# btnsm_a_bit_larger.net
KiCad netlist of a schematic drawn in EAGLE
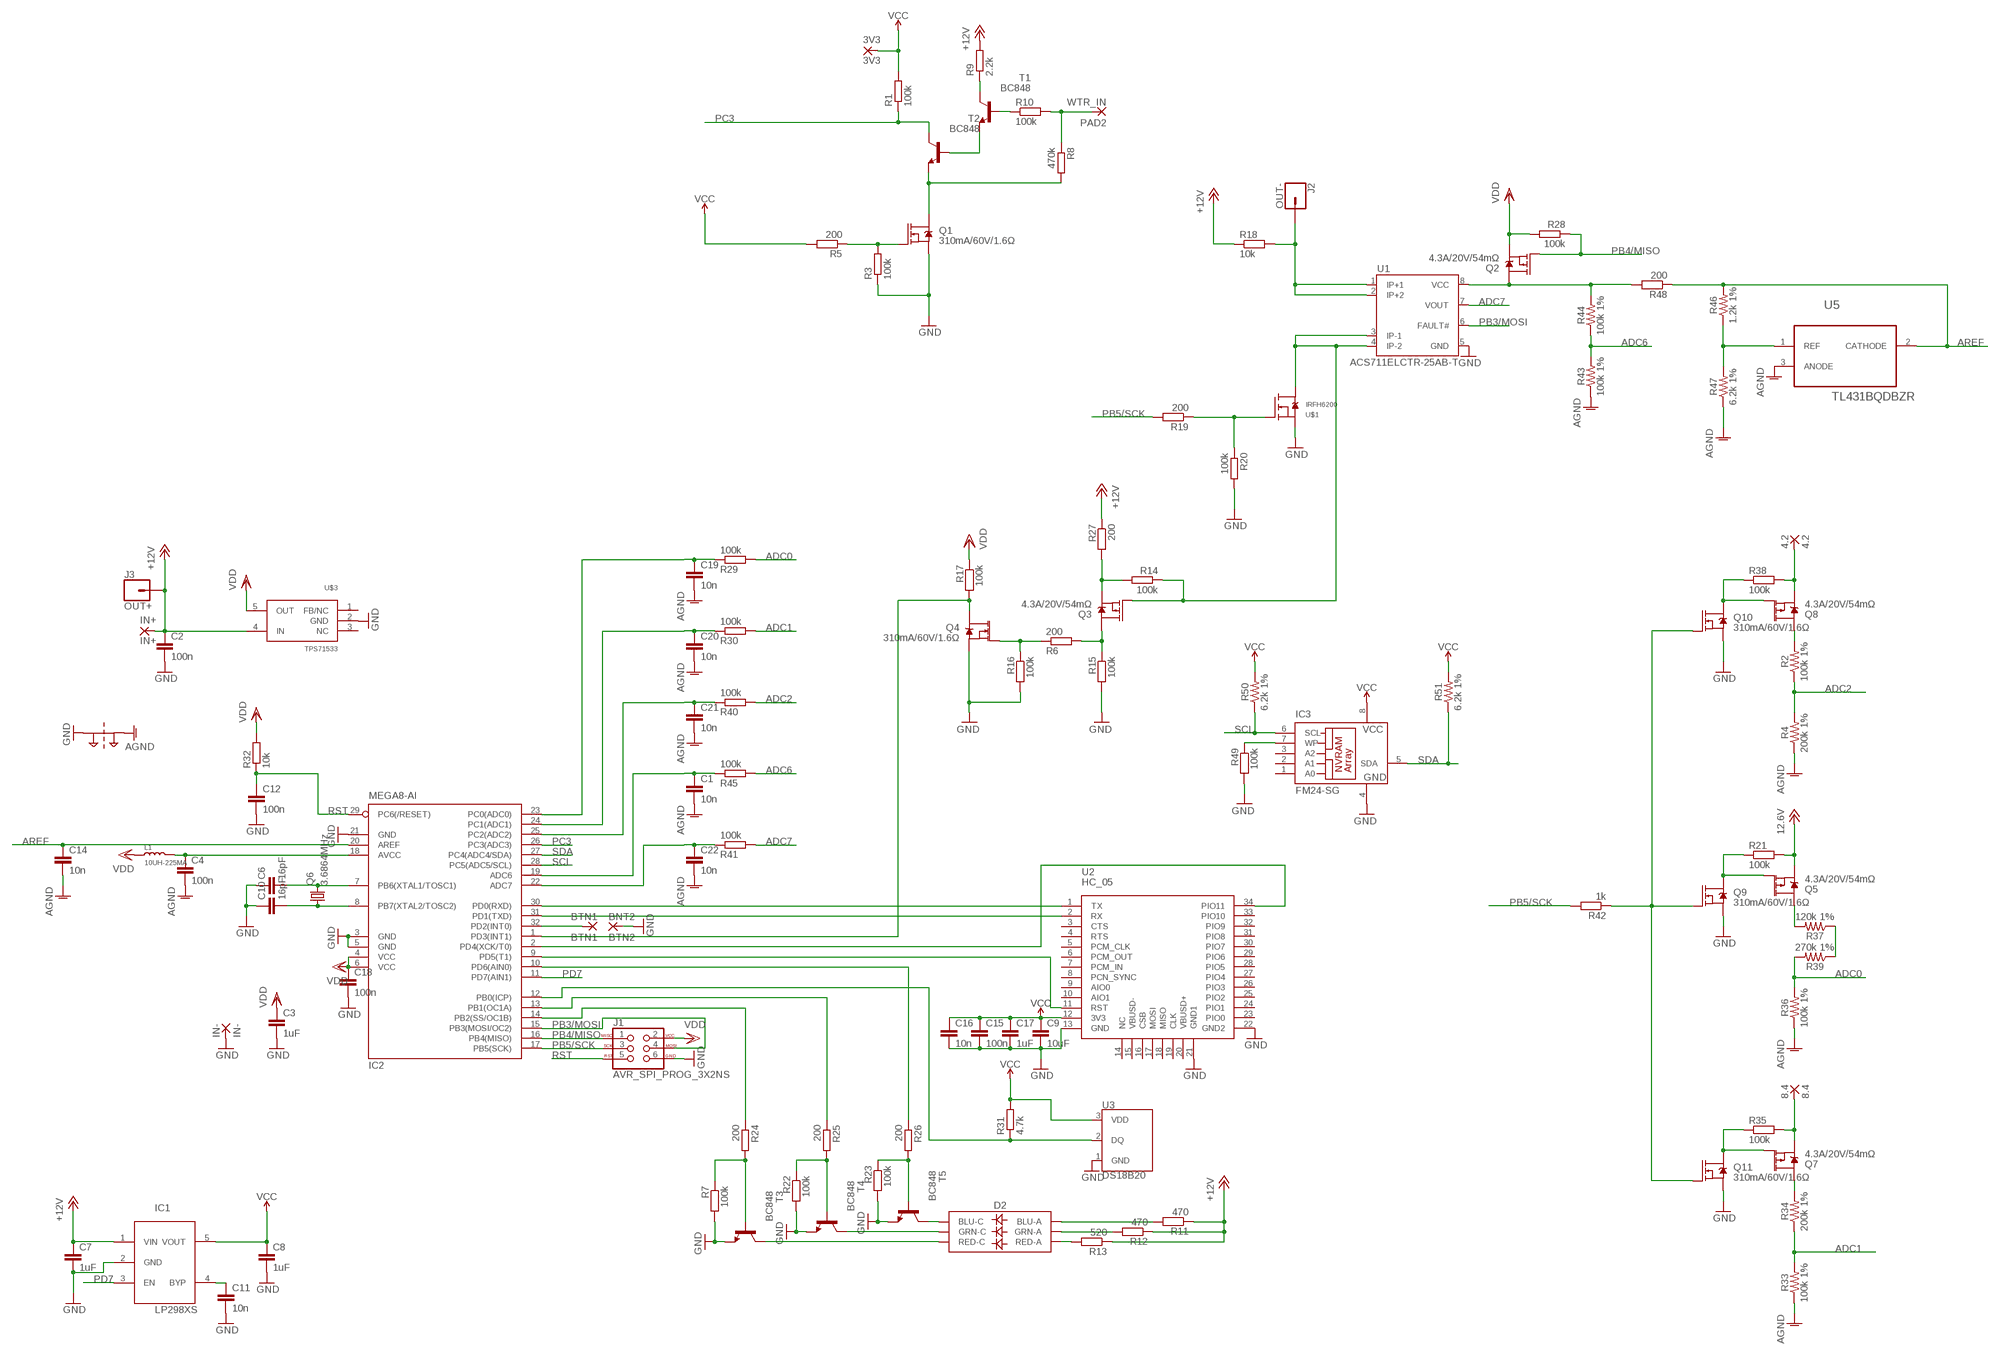
[diagram p0: schematic, sheet 1]

(export (version "E")
  (design (tool "Eeschema 10.0.6"))
  (components
    (comp (ref "3V3")
      (value "3V3")
      (footprint "eagle-import:SMD1,27-2,54")
      (libsource (lib "eagle-import") (part "WIREPADSMD1,27-254"))
    )
    (comp (ref "4.2")
      (value "4.2")
      (footprint "eagle-import:SMD1,27-2,54")
      (libsource (lib "eagle-import") (part "WIREPADSMD1,27-254"))
    )
    (comp (ref "8.4")
      (value "8.4")
      (footprint "eagle-import:SMD1,27-2,54")
      (libsource (lib "eagle-import") (part "WIREPADSMD1,27-254"))
    )
    (comp (ref "BTN1")
      (value "BTN1")
      (footprint "eagle-import:1,6_0,9")
      (libsource (lib "eagle-import") (part "1,6/0,9"))
    )
    (comp (ref "BTN2")
      (value "BNT2")
      (footprint "eagle-import:1,6_0,9")
      (libsource (lib "eagle-import") (part "1,6/0,9"))
    )
    (comp (ref "C1")
      (value "10n")
      (footprint "eagle-import:C0402")
      (libsource (lib "eagle-import") (part "C-EUC0402"))
    )
    (comp (ref "C2")
      (value "100n")
      (footprint "eagle-import:C0603")
      (libsource (lib "eagle-import") (part "C-EUC0603"))
    )
    (comp (ref "C3")
      (value "1uF")
      (footprint "eagle-import:C0805")
      (libsource (lib "eagle-import") (part "C-EUC0805"))
    )
    (comp (ref "C4")
      (value "100n")
      (footprint "eagle-import:C0402")
      (libsource (lib "eagle-import") (part "C-EUC0402"))
    )
    (comp (ref "C6")
      (value "16pF")
      (footprint "eagle-import:C0402")
      (libsource (lib "eagle-import") (part "C-EUC0402"))
    )
    (comp (ref "C7")
      (value "1uF")
      (footprint "eagle-import:C0805")
      (libsource (lib "eagle-import") (part "C-EUC0805"))
    )
    (comp (ref "C8")
      (value "1uF")
      (footprint "eagle-import:C0805")
      (libsource (lib "eagle-import") (part "C-EUC0805"))
    )
    (comp (ref "C9")
      (value "10uF")
      (footprint "eagle-import:C0805")
      (libsource (lib "eagle-import") (part "C-EUC0805"))
    )
    (comp (ref "C10")
      (value "16pF")
      (footprint "eagle-import:C0402")
      (libsource (lib "eagle-import") (part "C-EUC0402"))
    )
    (comp (ref "C11")
      (value "10n")
      (footprint "eagle-import:C0402")
      (libsource (lib "eagle-import") (part "C-EUC0402"))
    )
    (comp (ref "C12")
      (value "100n")
      (footprint "eagle-import:C0402")
      (libsource (lib "eagle-import") (part "C-EUC0402"))
    )
    (comp (ref "C14")
      (value "10n")
      (footprint "eagle-import:C0402")
      (libsource (lib "eagle-import") (part "C-EUC0402"))
    )
    (comp (ref "C15")
      (value "100n")
      (footprint "eagle-import:C0402")
      (libsource (lib "eagle-import") (part "C-EUC0402"))
    )
    (comp (ref "C16")
      (value "10n")
      (footprint "eagle-import:C0402")
      (libsource (lib "eagle-import") (part "C-EUC0402"))
    )
    (comp (ref "C17")
      (value "1uF")
      (footprint "eagle-import:C0805")
      (libsource (lib "eagle-import") (part "C-EUC0805"))
    )
    (comp (ref "C18")
      (value "100n")
      (footprint "eagle-import:C0402")
      (libsource (lib "eagle-import") (part "C-EUC0402"))
    )
    (comp (ref "C19")
      (value "10n")
      (footprint "eagle-import:C0402")
      (libsource (lib "eagle-import") (part "C-EUC0402"))
    )
    (comp (ref "C20")
      (value "10n")
      (footprint "eagle-import:C0402")
      (libsource (lib "eagle-import") (part "C-EUC0402"))
    )
    (comp (ref "C21")
      (value "10n")
      (footprint "eagle-import:C0402")
      (libsource (lib "eagle-import") (part "C-EUC0402"))
    )
    (comp (ref "C22")
      (value "10n")
      (footprint "eagle-import:C0402")
      (libsource (lib "eagle-import") (part "C-EUC0402"))
    )
    (comp (ref "D2")
      (value "LED-RGBNO_IC")
      (footprint "eagle-import:LED-TRICOLOR-5050")
      (libsource (lib "eagle-import") (part "LED-RGBNO_IC"))
    )
    (comp (ref "IC1")
      (value "LP298XS")
      (footprint "eagle-import:SOT23-5L")
      (libsource (lib "eagle-import") (part "LP298XS"))
    )
    (comp (ref "IC2")
      (value "MEGA8-AI")
      (footprint "eagle-import:TQFP32-08")
      (fields (field (name "MPN") "ATMEGA8-16AU"))
      (libsource (lib "eagle-import") (part "MEGA8-AI"))
    )
    (comp (ref "IC3")
      (value "FM24-SG")
      (footprint "eagle-import:SO8")
      (libsource (lib "eagle-import") (part "FM24-SG"))
    )
    (comp (ref "IN+")
      (value "IN+")
      (footprint "eagle-import:SMD2,54-5,08")
      (libsource (lib "eagle-import") (part "SMD5"))
    )
    (comp (ref "IN-")
      (value "IN-")
      (footprint "eagle-import:SMD2,54-5,08")
      (libsource (lib "eagle-import") (part "SMD5"))
    )
    (comp (ref "J1")
      (value "AVR_SPI_PROG_3X2NS")
      (footprint "eagle-import:2X3-NS")
      (libsource (lib "eagle-import") (part "AVR_SPI_PROG_3X2NS"))
    )
    (comp (ref "J2")
      (value "OUT-")
      (footprint "eagle-import:1X01_2MM")
      (libsource (lib "eagle-import") (part "CONN_01PTH_2MM"))
    )
    (comp (ref "J3")
      (value "OUT+")
      (footprint "eagle-import:1X01_2MM")
      (libsource (lib "eagle-import") (part "CONN_01PTH_2MM"))
    )
    (comp (ref "L1")
      (value "10UH-225MA")
      (footprint "eagle-import:L0806")
      (fields (field (name "MPN") "LQH2MCN100K02L"))
      (libsource (lib "eagle-import") (part "SMD-INDUCTOR-10UH-225MA-10%(0806)"))
    )
    (comp (ref "PAD2")
      (value "WTR_IN")
      (footprint "eagle-import:SMD1,27-2,54")
      (libsource (lib "eagle-import") (part "WIREPADSMD1,27-254"))
    )
    (comp (ref "Q1")
      (value "310mA/60V/1.6Ω")
      (footprint "eagle-import:SOT323")
      (libsource (lib "eagle-import") (part "MOSFET-NCH-2N7002PW"))
    )
    (comp (ref "Q2")
      (value "4.3A/20V/54mΩ")
      (footprint "eagle-import:SOT23-3")
      (libsource (lib "eagle-import") (part "MOSFET_PCH-IRLML2244"))
    )
    (comp (ref "Q3")
      (value "4.3A/20V/54mΩ")
      (footprint "eagle-import:SOT23-3")
      (libsource (lib "eagle-import") (part "MOSFET_PCH-IRLML2244"))
    )
    (comp (ref "Q4")
      (value "310mA/60V/1.6Ω")
      (footprint "eagle-import:SOT323")
      (libsource (lib "eagle-import") (part "MOSFET-NCH-2N7002PW"))
    )
    (comp (ref "Q5")
      (value "4.3A/20V/54mΩ")
      (footprint "eagle-import:SOT23-3")
      (libsource (lib "eagle-import") (part "MOSFET_PCH-IRLML2244"))
    )
    (comp (ref "Q6")
      (value "3.6864MHz")
      (footprint "eagle-import:HC49_S")
      (libsource (lib "eagle-import") (part "CRYSTALHC49S"))
    )
    (comp (ref "Q7")
      (value "4.3A/20V/54mΩ")
      (footprint "eagle-import:SOT23-3")
      (libsource (lib "eagle-import") (part "MOSFET_PCH-IRLML2244"))
    )
    (comp (ref "Q8")
      (value "4.3A/20V/54mΩ")
      (footprint "eagle-import:SOT23-3")
      (libsource (lib "eagle-import") (part "MOSFET_PCH-IRLML2244"))
    )
    (comp (ref "Q9")
      (value "310mA/60V/1.6Ω")
      (footprint "eagle-import:SOT323")
      (libsource (lib "eagle-import") (part "MOSFET-NCH-2N7002PW"))
    )
    (comp (ref "Q10")
      (value "310mA/60V/1.6Ω")
      (footprint "eagle-import:SOT323")
      (libsource (lib "eagle-import") (part "MOSFET-NCH-2N7002PW"))
    )
    (comp (ref "Q11")
      (value "310mA/60V/1.6Ω")
      (footprint "eagle-import:SOT323")
      (libsource (lib "eagle-import") (part "MOSFET-NCH-2N7002PW"))
    )
    (comp (ref "R1")
      (value "100k")
      (footprint "eagle-import:R0402")
      (libsource (lib "eagle-import") (part "R-EU_R0402"))
    )
    (comp (ref "R2")
      (value "100k 1%")
      (footprint "eagle-import:0805")
      (libsource (lib "eagle-import") (part "RESISTOR0805"))
    )
    (comp (ref "R3")
      (value "100k")
      (footprint "eagle-import:R0402")
      (libsource (lib "eagle-import") (part "R-EU_R0402"))
    )
    (comp (ref "R4")
      (value "200k 1%")
      (footprint "eagle-import:0805")
      (libsource (lib "eagle-import") (part "RESISTOR0805"))
    )
    (comp (ref "R5")
      (value "200")
      (footprint "eagle-import:R0402")
      (libsource (lib "eagle-import") (part "R-EU_R0402"))
    )
    (comp (ref "R6")
      (value "200")
      (footprint "eagle-import:R0402")
      (libsource (lib "eagle-import") (part "R-EU_R0402"))
    )
    (comp (ref "R7")
      (value "100k")
      (footprint "eagle-import:R0402")
      (libsource (lib "eagle-import") (part "R-EU_R0402"))
    )
    (comp (ref "R8")
      (value "470k")
      (footprint "eagle-import:R0402")
      (libsource (lib "eagle-import") (part "R-EU_R0402"))
    )
    (comp (ref "R9")
      (value "2.2k")
      (footprint "eagle-import:R0402")
      (libsource (lib "eagle-import") (part "R-EU_R0402"))
    )
    (comp (ref "R10")
      (value "100k")
      (footprint "eagle-import:R0402")
      (libsource (lib "eagle-import") (part "R-EU_R0402"))
    )
    (comp (ref "R11")
      (value "470")
      (footprint "eagle-import:R0805")
      (libsource (lib "eagle-import") (part "R-EU_R0805"))
    )
    (comp (ref "R12")
      (value "470")
      (footprint "eagle-import:R0805")
      (libsource (lib "eagle-import") (part "R-EU_R0805"))
    )
    (comp (ref "R13")
      (value "520")
      (footprint "eagle-import:R0805")
      (libsource (lib "eagle-import") (part "R-EU_R0805"))
    )
    (comp (ref "R14")
      (value "100k")
      (footprint "eagle-import:R0402")
      (libsource (lib "eagle-import") (part "R-EU_R0402"))
    )
    (comp (ref "R15")
      (value "100k")
      (footprint "eagle-import:R0402")
      (libsource (lib "eagle-import") (part "R-EU_R0402"))
    )
    (comp (ref "R16")
      (value "100k")
      (footprint "eagle-import:R0402")
      (libsource (lib "eagle-import") (part "R-EU_R0402"))
    )
    (comp (ref "R17")
      (value "100k")
      (footprint "eagle-import:R0402")
      (libsource (lib "eagle-import") (part "R-EU_R0402"))
    )
    (comp (ref "R18")
      (value "10k")
      (footprint "eagle-import:R0402")
      (libsource (lib "eagle-import") (part "R-EU_R0402"))
    )
    (comp (ref "R19")
      (value "200")
      (footprint "eagle-import:R0402")
      (libsource (lib "eagle-import") (part "R-EU_R0402"))
    )
    (comp (ref "R20")
      (value "100k")
      (footprint "eagle-import:R0402")
      (libsource (lib "eagle-import") (part "R-EU_R0402"))
    )
    (comp (ref "R21")
      (value "100k")
      (footprint "eagle-import:R0402")
      (libsource (lib "eagle-import") (part "R-EU_R0402"))
    )
    (comp (ref "R22")
      (value "100k")
      (footprint "eagle-import:R0402")
      (libsource (lib "eagle-import") (part "R-EU_R0402"))
    )
    (comp (ref "R23")
      (value "100k")
      (footprint "eagle-import:R0402")
      (libsource (lib "eagle-import") (part "R-EU_R0402"))
    )
    (comp (ref "R24")
      (value "200")
      (footprint "eagle-import:R0402")
      (libsource (lib "eagle-import") (part "R-EU_R0402"))
    )
    (comp (ref "R25")
      (value "200")
      (footprint "eagle-import:R0402")
      (libsource (lib "eagle-import") (part "R-EU_R0402"))
    )
    (comp (ref "R26")
      (value "200")
      (footprint "eagle-import:R0402")
      (libsource (lib "eagle-import") (part "R-EU_R0402"))
    )
    (comp (ref "R27")
      (value "200")
      (footprint "eagle-import:R0402")
      (libsource (lib "eagle-import") (part "R-EU_R0402"))
    )
    (comp (ref "R28")
      (value "100k")
      (footprint "eagle-import:R0402")
      (libsource (lib "eagle-import") (part "R-EU_R0402"))
    )
    (comp (ref "R29")
      (value "100k")
      (footprint "eagle-import:R0402")
      (libsource (lib "eagle-import") (part "R-EU_R0402"))
    )
    (comp (ref "R30")
      (value "100k")
      (footprint "eagle-import:R0402")
      (libsource (lib "eagle-import") (part "R-EU_R0402"))
    )
    (comp (ref "R31")
      (value "4.7k")
      (footprint "eagle-import:R0402")
      (libsource (lib "eagle-import") (part "R-EU_R0402"))
    )
    (comp (ref "R32")
      (value "10k")
      (footprint "eagle-import:R0402")
      (libsource (lib "eagle-import") (part "R-EU_R0402"))
    )
    (comp (ref "R33")
      (value "100k 1%")
      (footprint "eagle-import:0805")
      (libsource (lib "eagle-import") (part "RESISTOR0805"))
    )
    (comp (ref "R34")
      (value "200k 1%")
      (footprint "eagle-import:0805")
      (libsource (lib "eagle-import") (part "RESISTOR0805"))
    )
    (comp (ref "R35")
      (value "100k")
      (footprint "eagle-import:R0402")
      (libsource (lib "eagle-import") (part "R-EU_R0402"))
    )
    (comp (ref "R36")
      (value "100k 1%")
      (footprint "eagle-import:0805")
      (libsource (lib "eagle-import") (part "RESISTOR0805"))
    )
    (comp (ref "R37")
      (value "120k 1%")
      (footprint "eagle-import:0805")
      (libsource (lib "eagle-import") (part "RESISTOR0805"))
    )
    (comp (ref "R38")
      (value "100k")
      (footprint "eagle-import:R0402")
      (libsource (lib "eagle-import") (part "R-EU_R0402"))
    )
    (comp (ref "R39")
      (value "270k 1%")
      (footprint "eagle-import:0805")
      (libsource (lib "eagle-import") (part "RESISTOR0805"))
    )
    (comp (ref "R40")
      (value "100k")
      (footprint "eagle-import:R0402")
      (libsource (lib "eagle-import") (part "R-EU_R0402"))
    )
    (comp (ref "R41")
      (value "100k")
      (footprint "eagle-import:R0402")
      (libsource (lib "eagle-import") (part "R-EU_R0402"))
    )
    (comp (ref "R42")
      (value "1k")
      (footprint "eagle-import:R0402")
      (libsource (lib "eagle-import") (part "R-EU_R0402"))
    )
    (comp (ref "R43")
      (value "100k 1%")
      (footprint "eagle-import:0805")
      (libsource (lib "eagle-import") (part "RESISTOR0805"))
    )
    (comp (ref "R44")
      (value "100k 1%")
      (footprint "eagle-import:0805")
      (libsource (lib "eagle-import") (part "RESISTOR0805"))
    )
    (comp (ref "R45")
      (value "100k")
      (footprint "eagle-import:R0402")
      (libsource (lib "eagle-import") (part "R-EU_R0402"))
    )
    (comp (ref "R46")
      (value "1.2k 1%")
      (footprint "eagle-import:0805")
      (libsource (lib "eagle-import") (part "RESISTOR0805"))
    )
    (comp (ref "R47")
      (value "6.2k 1%")
      (footprint "eagle-import:0805")
      (libsource (lib "eagle-import") (part "RESISTOR0805"))
    )
    (comp (ref "R48")
      (value "200")
      (footprint "eagle-import:R0402")
      (libsource (lib "eagle-import") (part "R-EU_R0402"))
    )
    (comp (ref "R49")
      (value "100k")
      (footprint "eagle-import:R0402")
      (libsource (lib "eagle-import") (part "R-EU_R0402"))
    )
    (comp (ref "R50")
      (value "6.2k 1%")
      (footprint "eagle-import:0805")
      (libsource (lib "eagle-import") (part "RESISTOR0805"))
    )
    (comp (ref "R51")
      (value "6.2k 1%")
      (footprint "eagle-import:0805")
      (libsource (lib "eagle-import") (part "RESISTOR0805"))
    )
    (comp (ref "SUPPLY7")
      (value "2PT_GND_TIE")
      (footprint "eagle-import:2PT_GND_TIE")
      (libsource (lib "eagle-import") (part "2PT_GND_TIE"))
    )
    (comp (ref "T1")
      (value "BC848")
      (footprint "eagle-import:SOT23")
      (libsource (lib "eagle-import") (part "BC848"))
    )
    (comp (ref "T2")
      (value "BC848")
      (footprint "eagle-import:SOT23")
      (fields (field (name "SPICEPREFIX") "Q"))
      (libsource (lib "eagle-import") (part "BC848"))
    )
    (comp (ref "T3")
      (value "BC848")
      (footprint "eagle-import:SOT23")
      (libsource (lib "eagle-import") (part "BC848"))
    )
    (comp (ref "T4")
      (value "BC848")
      (footprint "eagle-import:SOT23")
      (libsource (lib "eagle-import") (part "BC848"))
    )
    (comp (ref "T5")
      (value "BC848")
      (footprint "eagle-import:SOT23")
      (libsource (lib "eagle-import") (part "BC848"))
    )
    (comp (ref "U$1")
      (value "IRFH6200")
      (footprint "eagle-import:PQFN")
      (libsource (lib "eagle-import") (part "IRFH6200"))
    )
    (comp (ref "U$3")
      (value "TPS71533")
      (footprint "eagle-import:SC70")
      (libsource (lib "eagle-import") (part "TPS715"))
    )
    (comp (ref "U1")
      (value "ACS711ELCTR-25AB-T")
      (footprint "eagle-import:SOIC8")
      (libsource (lib "eagle-import") (part "ACS711ELC?TR-25AB-T"))
    )
    (comp (ref "U2")
      (value "HC_05")
      (footprint "eagle-import:BLUETOOTH_SMD")
      (libsource (lib "eagle-import") (part "HC_05"))
    )
    (comp (ref "U3")
      (value "DS18B20")
      (footprint "eagle-import:TO-92-AMMO")
      (libsource (lib "eagle-import") (part "DS18B20"))
    )
    (comp (ref "U5")
      (value "TL431BQDBZR")
      (footprint "eagle-import:SOT95P237X112-3N")
      (libsource (lib "eagle-import") (part "TL431BQDBZR"))
    )
  )
  (nets
    (net (code "1") (name "+12V") (class "Default")
      (node (ref "C2") (pin "1") (pinfunction "1_1") (pintype "passive"))
      (node (ref "C7") (pin "1") (pinfunction "1_1") (pintype "passive"))
      (node (ref "IC1") (pin "1") (pinfunction "VIN_1") (pintype "bidirectional"))
      (node (ref "IN+") (pin "1") (pinfunction "P_1") (pintype "passive"))
      (node (ref "J3") (pin "1") (pinfunction "1_1") (pintype "passive"))
      (node (ref "Q5") (pin "2") (pinfunction "S_2") (pintype "bidirectional"))
      (node (ref "R11") (pin "1") (pinfunction "1_1") (pintype "passive"))
      (node (ref "R12") (pin "1") (pinfunction "1_1") (pintype "passive"))
      (node (ref "R13") (pin "1") (pinfunction "1_1") (pintype "passive"))
      (node (ref "R18") (pin "1") (pinfunction "1_1") (pintype "passive"))
      (node (ref "R21") (pin "2") (pinfunction "2_2") (pintype "passive"))
      (node (ref "R27") (pin "1") (pinfunction "1_1") (pintype "passive"))
      (node (ref "R9") (pin "2") (pinfunction "2_2") (pintype "passive"))
      (node (ref "U$3") (pin "4") (pinfunction "IN_4") (pintype "bidirectional"))
    )
    (net (code "2") (name "/ADC0") (class "Default")
      (node (ref "R29") (pin "2") (pinfunction "2_2") (pintype "passive"))
      (node (ref "R36") (pin "2") (pinfunction "2_2") (pintype "passive"))
      (node (ref "R39") (pin "2") (pinfunction "2_2") (pintype "passive"))
    )
    (net (code "3") (name "/ADC1") (class "Default")
      (node (ref "R30") (pin "2") (pinfunction "2_2") (pintype "passive"))
      (node (ref "R33") (pin "2") (pinfunction "2_2") (pintype "passive"))
      (node (ref "R34") (pin "1") (pinfunction "1_1") (pintype "passive"))
    )
    (net (code "4") (name "/ADC2") (class "Default")
      (node (ref "R2") (pin "1") (pinfunction "1_1") (pintype "passive"))
      (node (ref "R4") (pin "2") (pinfunction "2_2") (pintype "passive"))
      (node (ref "R40") (pin "2") (pinfunction "2_2") (pintype "passive"))
    )
    (net (code "5") (name "/ADC6") (class "Default")
      (node (ref "R43") (pin "2") (pinfunction "2_2") (pintype "passive"))
      (node (ref "R44") (pin "1") (pinfunction "1_1") (pintype "passive"))
      (node (ref "R45") (pin "2") (pinfunction "2_2") (pintype "passive"))
    )
    (net (code "6") (name "/ADC7") (class "Default")
      (node (ref "R41") (pin "2") (pinfunction "2_2") (pintype "passive"))
      (node (ref "U1") (pin "7") (pinfunction "VOUT_7") (pintype "bidirectional"))
    )
    (net (code "7") (name "/AREF") (class "Default")
      (node (ref "C14") (pin "1") (pinfunction "1_1") (pintype "passive"))
      (node (ref "IC2") (pin "20") (pinfunction "AREF_20") (pintype "passive"))
      (node (ref "R46") (pin "2") (pinfunction "2_2") (pintype "passive"))
      (node (ref "R48") (pin "1") (pinfunction "1_1") (pintype "passive"))
      (node (ref "U5") (pin "2") (pinfunction "CATHODE_2") (pintype "passive"))
    )
    (net (code "8") (name "/PB3{slash}MOSI") (class "Default")
      (node (ref "IC2") (pin "15") (pinfunction "PB3(MOSI/OC2)_15") (pintype "bidirectional"))
      (node (ref "J1") (pin "4") (pinfunction "4_4") (pintype "passive"))
      (node (ref "U1") (pin "6") (pinfunction "FAULT#_6") (pintype "bidirectional"))
    )
    (net (code "9") (name "/PB4{slash}MISO") (class "Default")
      (node (ref "IC2") (pin "16") (pinfunction "PB4(MISO)_16") (pintype "bidirectional"))
      (node (ref "J1") (pin "1") (pinfunction "1_1") (pintype "passive"))
      (node (ref "Q2") (pin "1") (pinfunction "G_1") (pintype "bidirectional"))
      (node (ref "R28") (pin "1") (pinfunction "1_1") (pintype "passive"))
    )
    (net (code "10") (name "/PB5{slash}SCK") (class "Default")
      (node (ref "IC2") (pin "17") (pinfunction "PB5(SCK)_17") (pintype "bidirectional"))
      (node (ref "J1") (pin "3") (pinfunction "3_3") (pintype "passive"))
      (node (ref "R19") (pin "2") (pinfunction "2_2") (pintype "passive"))
      (node (ref "R42") (pin "2") (pinfunction "2_2") (pintype "passive"))
    )
    (net (code "11") (name "/PC3") (class "Default")
      (node (ref "IC2") (pin "26") (pinfunction "PC3(ADC3)_26") (pintype "bidirectional"))
      (node (ref "R1") (pin "1") (pinfunction "1_1") (pintype "passive"))
      (node (ref "T2") (pin "3") (pinfunction "C_3") (pintype "passive"))
    )
    (net (code "12") (name "/PD7") (class "Default")
      (node (ref "IC1") (pin "3") (pinfunction "EN_3") (pintype "bidirectional"))
      (node (ref "IC2") (pin "11") (pinfunction "PD7(AIN1)_11") (pintype "bidirectional"))
    )
    (net (code "13") (name "/RST") (class "Default")
      (node (ref "C12") (pin "1") (pinfunction "1_1") (pintype "passive"))
      (node (ref "IC2") (pin "29") (pinfunction "PC6(/RESET)_29") (pintype "bidirectional"))
      (node (ref "J1") (pin "5") (pinfunction "5_5") (pintype "passive"))
      (node (ref "R32") (pin "1") (pinfunction "1_1") (pintype "passive"))
    )
    (net (code "14") (name "/SCL") (class "Default")
      (node (ref "IC2") (pin "28") (pinfunction "PC5(ADC5/SCL)_28") (pintype "bidirectional"))
      (node (ref "IC3") (pin "6") (pinfunction "SCL_6") (pintype "input"))
      (node (ref "R50") (pin "1") (pinfunction "1_1") (pintype "passive"))
    )
    (net (code "15") (name "/SDA") (class "Default")
      (node (ref "IC2") (pin "27") (pinfunction "PC4(ADC4/SDA)_27") (pintype "bidirectional"))
      (node (ref "IC3") (pin "5") (pinfunction "SDA_5") (pintype "bidirectional"))
      (node (ref "R51") (pin "1") (pinfunction "1_1") (pintype "passive"))
    )
    (net (code "16") (name "AGND") (class "Default")
      (node (ref "C1") (pin "2") (pinfunction "2_2") (pintype "passive"))
      (node (ref "C14") (pin "2") (pinfunction "2_2") (pintype "passive"))
      (node (ref "C19") (pin "2") (pinfunction "2_2") (pintype "passive"))
      (node (ref "C20") (pin "2") (pinfunction "2_2") (pintype "passive"))
      (node (ref "C21") (pin "2") (pinfunction "2_2") (pintype "passive"))
      (node (ref "C22") (pin "2") (pinfunction "2_2") (pintype "passive"))
      (node (ref "C4") (pin "2") (pinfunction "2_2") (pintype "passive"))
      (node (ref "R33") (pin "1") (pinfunction "1_1") (pintype "passive"))
      (node (ref "R36") (pin "1") (pinfunction "1_1") (pintype "passive"))
      (node (ref "R4") (pin "1") (pinfunction "1_1") (pintype "passive"))
      (node (ref "R43") (pin "1") (pinfunction "1_1") (pintype "passive"))
      (node (ref "R47") (pin "1") (pinfunction "1_1") (pintype "passive"))
      (node (ref "SUPPLY7") (pin "P$2") (pinfunction "P$2_P$2") (pintype "bidirectional"))
      (node (ref "U5") (pin "3") (pinfunction "ANODE_3") (pintype "passive"))
    )
    (net (code "17") (name "GND") (class "Default")
      (node (ref "BTN2") (pin "1") (pinfunction "P_1") (pintype "passive"))
      (node (ref "C10") (pin "1") (pinfunction "1_1") (pintype "passive"))
      (node (ref "C11") (pin "2") (pinfunction "2_2") (pintype "passive"))
      (node (ref "C12") (pin "2") (pinfunction "2_2") (pintype "passive"))
      (node (ref "C15") (pin "2") (pinfunction "2_2") (pintype "passive"))
      (node (ref "C16") (pin "2") (pinfunction "2_2") (pintype "passive"))
      (node (ref "C17") (pin "2") (pinfunction "2_2") (pintype "passive"))
      (node (ref "C18") (pin "2") (pinfunction "2_2") (pintype "passive"))
      (node (ref "C2") (pin "2") (pinfunction "2_2") (pintype "passive"))
      (node (ref "C3") (pin "2") (pinfunction "2_2") (pintype "passive"))
      (node (ref "C6") (pin "1") (pinfunction "1_1") (pintype "passive"))
      (node (ref "C7") (pin "2") (pinfunction "2_2") (pintype "passive"))
      (node (ref "C8") (pin "2") (pinfunction "2_2") (pintype "passive"))
      (node (ref "C9") (pin "2") (pinfunction "2_2") (pintype "passive"))
      (node (ref "IC1") (pin "2") (pinfunction "GND_2") (pintype "bidirectional"))
      (node (ref "IC2") (pin "21") (pinfunction "GND_21") (pintype "power_in"))
      (node (ref "IC2") (pin "3") (pinfunction "GND_3") (pintype "power_in"))
      (node (ref "IC2") (pin "5") (pinfunction "GND_5") (pintype "power_in"))
      (node (ref "IC3") (pin "4") (pinfunction "GND_4") (pintype "power_in"))
      (node (ref "IN-") (pin "1") (pinfunction "P_1") (pintype "passive"))
      (node (ref "J1") (pin "6") (pinfunction "6_6") (pintype "passive"))
      (node (ref "Q1") (pin "2") (pinfunction "S_2") (pintype "bidirectional"))
      (node (ref "Q10") (pin "2") (pinfunction "S_2") (pintype "bidirectional"))
      (node (ref "Q11") (pin "2") (pinfunction "S_2") (pintype "bidirectional"))
      (node (ref "Q4") (pin "2") (pinfunction "S_2") (pintype "bidirectional"))
      (node (ref "Q9") (pin "2") (pinfunction "S_2") (pintype "bidirectional"))
      (node (ref "R15") (pin "2") (pinfunction "2_2") (pintype "passive"))
      (node (ref "R16") (pin "2") (pinfunction "2_2") (pintype "passive"))
      (node (ref "R20") (pin "2") (pinfunction "2_2") (pintype "passive"))
      (node (ref "R22") (pin "2") (pinfunction "2_2") (pintype "passive"))
      (node (ref "R23") (pin "2") (pinfunction "2_2") (pintype "passive"))
      (node (ref "R3") (pin "1") (pinfunction "1_1") (pintype "passive"))
      (node (ref "R49") (pin "2") (pinfunction "2_2") (pintype "passive"))
      (node (ref "R7") (pin "2") (pinfunction "2_2") (pintype "passive"))
      (node (ref "SUPPLY7") (pin "P$1") (pinfunction "P$1_P$1") (pintype "bidirectional"))
      (node (ref "T3") (pin "2") (pinfunction "E_2") (pintype "passive"))
      (node (ref "T4") (pin "2") (pinfunction "E_2") (pintype "passive"))
      (node (ref "T5") (pin "2") (pinfunction "E_2") (pintype "passive"))
      (node (ref "U$1") (pin "1") (pinfunction "S_1") (pintype "power_in"))
      (node (ref "U$1") (pin "2") (pinfunction "S_2") (pintype "power_in"))
      (node (ref "U$1") (pin "3") (pinfunction "S_3") (pintype "power_in"))
      (node (ref "U$3") (pin "2") (pinfunction "GND_2") (pintype "bidirectional"))
      (node (ref "U1") (pin "5") (pinfunction "GND_5") (pintype "bidirectional"))
      (node (ref "U2") (pin "13") (pinfunction "GND_13") (pintype "bidirectional"))
      (node (ref "U2") (pin "21") (pinfunction "GND1_21") (pintype "bidirectional"))
      (node (ref "U2") (pin "22") (pinfunction "GND2_22") (pintype "bidirectional"))
      (node (ref "U3") (pin "1") (pinfunction "GND_1") (pintype "power_in"))
    )
    (net (code "18") (name "Net-(4.2-P)") (class "Default")
      (node (ref "4.2") (pin "1") (pinfunction "P_1") (pintype "passive"))
      (node (ref "Q8") (pin "2") (pinfunction "S_2") (pintype "bidirectional"))
      (node (ref "R38") (pin "2") (pinfunction "2_2") (pintype "passive"))
    )
    (net (code "19") (name "Net-(8.4-P)") (class "Default")
      (node (ref "8.4") (pin "1") (pinfunction "P_1") (pintype "passive"))
      (node (ref "Q7") (pin "2") (pinfunction "S_2") (pintype "bidirectional"))
      (node (ref "R35") (pin "2") (pinfunction "2_2") (pintype "passive"))
    )
    (net (code "20") (name "Net-(BTN1-P)") (class "Default")
      (node (ref "BTN1") (pin "1") (pinfunction "P_1") (pintype "passive"))
      (node (ref "IC2") (pin "32") (pinfunction "PD2(INT0)_32") (pintype "bidirectional"))
    )
    (net (code "21") (name "Net-(D2-BLU-A)") (class "Default")
      (node (ref "D2") (pin "3") (pinfunction "BLU-A_3") (pintype "bidirectional"))
      (node (ref "R11") (pin "2") (pinfunction "2_2") (pintype "passive"))
    )
    (net (code "22") (name "Net-(D2-BLU-C)") (class "Default")
      (node (ref "D2") (pin "4") (pinfunction "BLU-C_4") (pintype "bidirectional"))
      (node (ref "T5") (pin "3") (pinfunction "C_3") (pintype "passive"))
    )
    (net (code "23") (name "Net-(D2-GRN-A)") (class "Default")
      (node (ref "D2") (pin "1") (pinfunction "GRN-A_1") (pintype "bidirectional"))
      (node (ref "R12") (pin "2") (pinfunction "2_2") (pintype "passive"))
    )
    (net (code "24") (name "Net-(D2-GRN-C)") (class "Default")
      (node (ref "D2") (pin "6") (pinfunction "GRN-C_6") (pintype "bidirectional"))
      (node (ref "T4") (pin "3") (pinfunction "C_3") (pintype "passive"))
    )
    (net (code "25") (name "Net-(D2-RED-A)") (class "Default")
      (node (ref "D2") (pin "2") (pinfunction "RED-A_2") (pintype "bidirectional"))
      (node (ref "R13") (pin "2") (pinfunction "2_2") (pintype "passive"))
    )
    (net (code "26") (name "Net-(D2-RED-C)") (class "Default")
      (node (ref "D2") (pin "5") (pinfunction "RED-C_5") (pintype "bidirectional"))
      (node (ref "T3") (pin "3") (pinfunction "C_3") (pintype "passive"))
    )
    (net (code "27") (name "Net-(IC1-BYP)") (class "Default")
      (node (ref "C11") (pin "1") (pinfunction "1_1") (pintype "passive"))
      (node (ref "IC1") (pin "4") (pinfunction "BYP_4") (pintype "bidirectional"))
    )
    (net (code "28") (name "Net-(IC2-ADC6)") (class "Default")
      (node (ref "C1") (pin "1") (pinfunction "1_1") (pintype "passive"))
      (node (ref "IC2") (pin "19") (pinfunction "ADC6_19") (pintype "bidirectional"))
      (node (ref "R45") (pin "1") (pinfunction "1_1") (pintype "passive"))
    )
    (net (code "29") (name "Net-(IC2-ADC7)") (class "Default")
      (node (ref "C22") (pin "1") (pinfunction "1_1") (pintype "passive"))
      (node (ref "IC2") (pin "22") (pinfunction "ADC7_22") (pintype "bidirectional"))
      (node (ref "R41") (pin "1") (pinfunction "1_1") (pintype "passive"))
    )
    (net (code "30") (name "Net-(IC2-AVCC)") (class "Default")
      (node (ref "C4") (pin "1") (pinfunction "1_1") (pintype "passive"))
      (node (ref "IC2") (pin "18") (pinfunction "AVCC_18") (pintype "power_in"))
      (node (ref "L1") (pin "2") (pinfunction "2_2") (pintype "passive"))
    )
    (net (code "31") (name "Net-(IC2-PB0(ICP))") (class "Default")
      (node (ref "IC2") (pin "12") (pinfunction "PB0(ICP)_12") (pintype "bidirectional"))
      (node (ref "R31") (pin "1") (pinfunction "1_1") (pintype "passive"))
      (node (ref "U3") (pin "2") (pinfunction "DQ_2") (pintype "bidirectional"))
    )
    (net (code "32") (name "Net-(IC2-PB1(OC1A))") (class "Default")
      (node (ref "IC2") (pin "13") (pinfunction "PB1(OC1A)_13") (pintype "bidirectional"))
      (node (ref "R25") (pin "1") (pinfunction "1_1") (pintype "passive"))
    )
    (net (code "33") (name "Net-(IC2-PB2(SS{slash}OC1B))") (class "Default")
      (node (ref "IC2") (pin "14") (pinfunction "PB2(SS/OC1B)_14") (pintype "bidirectional"))
      (node (ref "R24") (pin "1") (pinfunction "1_1") (pintype "passive"))
    )
    (net (code "34") (name "Net-(IC2-PB6(XTAL1{slash}TOSC1))") (class "Default")
      (node (ref "C6") (pin "2") (pinfunction "2_2") (pintype "passive"))
      (node (ref "IC2") (pin "7") (pinfunction "PB6(XTAL1/TOSC1)_7") (pintype "bidirectional"))
      (node (ref "Q6") (pin "2") (pinfunction "2_2") (pintype "passive"))
    )
    (net (code "35") (name "Net-(IC2-PB7(XTAL2{slash}TOSC2))") (class "Default")
      (node (ref "C10") (pin "2") (pinfunction "2_2") (pintype "passive"))
      (node (ref "IC2") (pin "8") (pinfunction "PB7(XTAL2/TOSC2)_8") (pintype "bidirectional"))
      (node (ref "Q6") (pin "1") (pinfunction "1_1") (pintype "passive"))
    )
    (net (code "36") (name "Net-(IC2-PC0(ADC0))") (class "Default")
      (node (ref "C19") (pin "1") (pinfunction "1_1") (pintype "passive"))
      (node (ref "IC2") (pin "23") (pinfunction "PC0(ADC0)_23") (pintype "bidirectional"))
      (node (ref "R29") (pin "1") (pinfunction "1_1") (pintype "passive"))
    )
    (net (code "37") (name "Net-(IC2-PC1(ADC1))") (class "Default")
      (node (ref "C20") (pin "1") (pinfunction "1_1") (pintype "passive"))
      (node (ref "IC2") (pin "24") (pinfunction "PC1(ADC1)_24") (pintype "bidirectional"))
      (node (ref "R30") (pin "1") (pinfunction "1_1") (pintype "passive"))
    )
    (net (code "38") (name "Net-(IC2-PC2(ADC2))") (class "Default")
      (node (ref "C21") (pin "1") (pinfunction "1_1") (pintype "passive"))
      (node (ref "IC2") (pin "25") (pinfunction "PC2(ADC2)_25") (pintype "bidirectional"))
      (node (ref "R40") (pin "1") (pinfunction "1_1") (pintype "passive"))
    )
    (net (code "39") (name "Net-(IC2-PD0(RXD))") (class "Default")
      (node (ref "IC2") (pin "30") (pinfunction "PD0(RXD)_30") (pintype "bidirectional"))
      (node (ref "U2") (pin "1") (pinfunction "TX_1") (pintype "bidirectional"))
    )
    (net (code "40") (name "Net-(IC2-PD1(TXD))") (class "Default")
      (node (ref "IC2") (pin "31") (pinfunction "PD1(TXD)_31") (pintype "bidirectional"))
      (node (ref "U2") (pin "2") (pinfunction "RX_2") (pintype "bidirectional"))
    )
    (net (code "41") (name "Net-(IC2-PD3(INT1))") (class "Default")
      (node (ref "IC2") (pin "1") (pinfunction "PD3(INT1)_1") (pintype "bidirectional"))
      (node (ref "Q4") (pin "3") (pinfunction "D_3") (pintype "bidirectional"))
      (node (ref "R17") (pin "2") (pinfunction "2_2") (pintype "passive"))
    )
    (net (code "42") (name "Net-(IC2-PD4(XCK{slash}T0))") (class "Default")
      (node (ref "IC2") (pin "2") (pinfunction "PD4(XCK/T0)_2") (pintype "bidirectional"))
      (node (ref "U2") (pin "34") (pinfunction "PIO11_34") (pintype "bidirectional"))
    )
    (net (code "43") (name "Net-(IC2-PD5(T1))") (class "Default")
      (node (ref "IC2") (pin "9") (pinfunction "PD5(T1)_9") (pintype "bidirectional"))
      (node (ref "U2") (pin "11") (pinfunction "RST_11") (pintype "bidirectional"))
    )
    (net (code "44") (name "Net-(IC2-PD6(AIN0))") (class "Default")
      (node (ref "IC2") (pin "10") (pinfunction "PD6(AIN0)_10") (pintype "bidirectional"))
      (node (ref "R26") (pin "1") (pinfunction "1_1") (pintype "passive"))
    )
    (net (code "45") (name "Net-(IC3-WP)") (class "Default")
      (node (ref "IC3") (pin "7") (pinfunction "WP_7") (pintype "input"))
      (node (ref "R49") (pin "1") (pinfunction "1_1") (pintype "passive"))
    )
    (net (code "46") (name "Net-(PAD2-P)") (class "Default")
      (node (ref "PAD2") (pin "1") (pinfunction "P_1") (pintype "passive"))
      (node (ref "R10") (pin "2") (pinfunction "2_2") (pintype "passive"))
      (node (ref "R8") (pin "1") (pinfunction "1_1") (pintype "passive"))
    )
    (net (code "47") (name "Net-(Q1-D)") (class "Default")
      (node (ref "Q1") (pin "3") (pinfunction "D_3") (pintype "bidirectional"))
      (node (ref "R8") (pin "2") (pinfunction "2_2") (pintype "passive"))
      (node (ref "T2") (pin "2") (pinfunction "E_2") (pintype "passive"))
    )
    (net (code "48") (name "Net-(Q1-G)") (class "Default")
      (node (ref "Q1") (pin "1") (pinfunction "G_1") (pintype "bidirectional"))
      (node (ref "R3") (pin "2") (pinfunction "2_2") (pintype "passive"))
      (node (ref "R5") (pin "1") (pinfunction "1_1") (pintype "passive"))
    )
    (net (code "49") (name "Net-(Q2-D)") (class "Default")
      (node (ref "Q2") (pin "3") (pinfunction "D_3") (pintype "bidirectional"))
      (node (ref "R44") (pin "2") (pinfunction "2_2") (pintype "passive"))
      (node (ref "R48") (pin "2") (pinfunction "2_2") (pintype "passive"))
      (node (ref "U1") (pin "8") (pinfunction "VCC_8") (pintype "bidirectional"))
    )
    (net (code "50") (name "Net-(Q3-D)") (class "Default")
      (node (ref "Q3") (pin "3") (pinfunction "D_3") (pintype "bidirectional"))
      (node (ref "R15") (pin "1") (pinfunction "1_1") (pintype "passive"))
      (node (ref "R6") (pin "2") (pinfunction "2_2") (pintype "passive"))
    )
    (net (code "51") (name "Net-(Q3-G)") (class "Default")
      (node (ref "Q3") (pin "1") (pinfunction "G_1") (pintype "bidirectional"))
      (node (ref "R14") (pin "1") (pinfunction "1_1") (pintype "passive"))
      (node (ref "U$1") (pin "5") (pinfunction "D_5") (pintype "power_in"))
      (node (ref "U$1") (pin "6") (pinfunction "D_6") (pintype "power_in"))
      (node (ref "U$1") (pin "7") (pinfunction "D_7") (pintype "power_in"))
      (node (ref "U$1") (pin "8") (pinfunction "D_8") (pintype "power_in"))
      (node (ref "U$1") (pin "9") (pinfunction "D_9") (pintype "power_in"))
      (node (ref "U1") (pin "3") (pinfunction "IP-1_3") (pintype "bidirectional"))
      (node (ref "U1") (pin "4") (pinfunction "IP-2_4") (pintype "bidirectional"))
    )
    (net (code "52") (name "Net-(Q3-S)") (class "Default")
      (node (ref "Q3") (pin "2") (pinfunction "S_2") (pintype "bidirectional"))
      (node (ref "R14") (pin "2") (pinfunction "2_2") (pintype "passive"))
      (node (ref "R27") (pin "2") (pinfunction "2_2") (pintype "passive"))
    )
    (net (code "53") (name "Net-(Q4-G)") (class "Default")
      (node (ref "Q4") (pin "1") (pinfunction "G_1") (pintype "bidirectional"))
      (node (ref "R16") (pin "1") (pinfunction "1_1") (pintype "passive"))
      (node (ref "R6") (pin "1") (pinfunction "1_1") (pintype "passive"))
    )
    (net (code "54") (name "Net-(Q5-D)") (class "Default")
      (node (ref "Q5") (pin "3") (pinfunction "D_3") (pintype "bidirectional"))
      (node (ref "R37") (pin "2") (pinfunction "2_2") (pintype "passive"))
    )
    (net (code "55") (name "Net-(Q5-G)") (class "Default")
      (node (ref "Q5") (pin "1") (pinfunction "G_1") (pintype "bidirectional"))
      (node (ref "Q9") (pin "3") (pinfunction "D_3") (pintype "bidirectional"))
      (node (ref "R21") (pin "1") (pinfunction "1_1") (pintype "passive"))
    )
    (net (code "56") (name "Net-(Q7-D)") (class "Default")
      (node (ref "Q7") (pin "3") (pinfunction "D_3") (pintype "bidirectional"))
      (node (ref "R34") (pin "2") (pinfunction "2_2") (pintype "passive"))
    )
    (net (code "57") (name "Net-(Q8-D)") (class "Default")
      (node (ref "Q8") (pin "3") (pinfunction "D_3") (pintype "bidirectional"))
      (node (ref "R2") (pin "2") (pinfunction "2_2") (pintype "passive"))
    )
    (net (code "58") (name "Net-(Q10-D)") (class "Default")
      (node (ref "Q10") (pin "3") (pinfunction "D_3") (pintype "bidirectional"))
      (node (ref "Q8") (pin "1") (pinfunction "G_1") (pintype "bidirectional"))
      (node (ref "R38") (pin "1") (pinfunction "1_1") (pintype "passive"))
    )
    (net (code "59") (name "Net-(Q10-G)") (class "Default")
      (node (ref "Q10") (pin "1") (pinfunction "G_1") (pintype "bidirectional"))
      (node (ref "Q11") (pin "1") (pinfunction "G_1") (pintype "bidirectional"))
      (node (ref "Q9") (pin "1") (pinfunction "G_1") (pintype "bidirectional"))
      (node (ref "R42") (pin "1") (pinfunction "1_1") (pintype "passive"))
    )
    (net (code "60") (name "Net-(Q11-D)") (class "Default")
      (node (ref "Q11") (pin "3") (pinfunction "D_3") (pintype "bidirectional"))
      (node (ref "Q7") (pin "1") (pinfunction "G_1") (pintype "bidirectional"))
      (node (ref "R35") (pin "1") (pinfunction "1_1") (pintype "passive"))
    )
    (net (code "61") (name "Net-(R37-Pad1)") (class "Default")
      (node (ref "R37") (pin "1") (pinfunction "1_1") (pintype "passive"))
      (node (ref "R39") (pin "1") (pinfunction "1_1") (pintype "passive"))
    )
    (net (code "62") (name "Net-(T1-B)") (class "Default")
      (node (ref "R10") (pin "1") (pinfunction "1_1") (pintype "passive"))
      (node (ref "T1") (pin "1") (pinfunction "B_1") (pintype "passive"))
    )
    (net (code "63") (name "Net-(T1-C)") (class "Default")
      (node (ref "R9") (pin "1") (pinfunction "1_1") (pintype "passive"))
      (node (ref "T1") (pin "3") (pinfunction "C_3") (pintype "passive"))
    )
    (net (code "64") (name "Net-(T1-E)") (class "Default")
      (node (ref "T1") (pin "2") (pinfunction "E_2") (pintype "passive"))
      (node (ref "T2") (pin "1") (pinfunction "B_1") (pintype "passive"))
    )
    (net (code "65") (name "Net-(T3-B)") (class "Default")
      (node (ref "R24") (pin "2") (pinfunction "2_2") (pintype "passive"))
      (node (ref "R7") (pin "1") (pinfunction "1_1") (pintype "passive"))
      (node (ref "T3") (pin "1") (pinfunction "B_1") (pintype "passive"))
    )
    (net (code "66") (name "Net-(T4-B)") (class "Default")
      (node (ref "R22") (pin "1") (pinfunction "1_1") (pintype "passive"))
      (node (ref "R25") (pin "2") (pinfunction "2_2") (pintype "passive"))
      (node (ref "T4") (pin "1") (pinfunction "B_1") (pintype "passive"))
    )
    (net (code "67") (name "Net-(T5-B)") (class "Default")
      (node (ref "R23") (pin "1") (pinfunction "1_1") (pintype "passive"))
      (node (ref "R26") (pin "2") (pinfunction "2_2") (pintype "passive"))
      (node (ref "T5") (pin "1") (pinfunction "B_1") (pintype "passive"))
    )
    (net (code "68") (name "Net-(U$1-G)") (class "Default")
      (node (ref "R19") (pin "1") (pinfunction "1_1") (pintype "passive"))
      (node (ref "R20") (pin "1") (pinfunction "1_1") (pintype "passive"))
      (node (ref "U$1") (pin "4") (pinfunction "G_4") (pintype "bidirectional"))
    )
    (net (code "69") (name "Net-(U1-IP+1)") (class "Default")
      (node (ref "J2") (pin "1") (pinfunction "1_1") (pintype "passive"))
      (node (ref "R18") (pin "2") (pinfunction "2_2") (pintype "passive"))
      (node (ref "U1") (pin "1") (pinfunction "IP+1_1") (pintype "bidirectional"))
      (node (ref "U1") (pin "2") (pinfunction "IP+2_2") (pintype "bidirectional"))
    )
    (net (code "70") (name "Net-(U5-REF)") (class "Default")
      (node (ref "R46") (pin "1") (pinfunction "1_1") (pintype "passive"))
      (node (ref "R47") (pin "2") (pinfunction "2_2") (pintype "passive"))
      (node (ref "U5") (pin "1") (pinfunction "REF_1") (pintype "power_in"))
    )
    (net (code "71") (name "VCC") (class "Default")
      (node (ref "3V3") (pin "1") (pinfunction "P_1") (pintype "passive"))
      (node (ref "C15") (pin "1") (pinfunction "1_1") (pintype "passive"))
      (node (ref "C16") (pin "1") (pinfunction "1_1") (pintype "passive"))
      (node (ref "C17") (pin "1") (pinfunction "1_1") (pintype "passive"))
      (node (ref "C8") (pin "1") (pinfunction "1_1") (pintype "passive"))
      (node (ref "C9") (pin "1") (pinfunction "1_1") (pintype "passive"))
      (node (ref "IC1") (pin "5") (pinfunction "VOUT_5") (pintype "bidirectional"))
      (node (ref "IC3") (pin "8") (pinfunction "VCC_8") (pintype "power_in"))
      (node (ref "R1") (pin "2") (pinfunction "2_2") (pintype "passive"))
      (node (ref "R31") (pin "2") (pinfunction "2_2") (pintype "passive"))
      (node (ref "R5") (pin "2") (pinfunction "2_2") (pintype "passive"))
      (node (ref "R50") (pin "2") (pinfunction "2_2") (pintype "passive"))
      (node (ref "R51") (pin "2") (pinfunction "2_2") (pintype "passive"))
      (node (ref "U2") (pin "12") (pinfunction "3V3_12") (pintype "bidirectional"))
      (node (ref "U3") (pin "3") (pinfunction "VDD_3") (pintype "power_in"))
    )
    (net (code "72") (name "VDD") (class "Default")
      (node (ref "C18") (pin "1") (pinfunction "1_1") (pintype "passive"))
      (node (ref "C3") (pin "1") (pinfunction "1_1") (pintype "passive"))
      (node (ref "IC2") (pin "4") (pinfunction "VCC_4") (pintype "power_in"))
      (node (ref "IC2") (pin "6") (pinfunction "VCC_6") (pintype "power_in"))
      (node (ref "J1") (pin "2") (pinfunction "2_2") (pintype "passive"))
      (node (ref "L1") (pin "1") (pinfunction "1_1") (pintype "passive"))
      (node (ref "Q2") (pin "2") (pinfunction "S_2") (pintype "bidirectional"))
      (node (ref "R17") (pin "1") (pinfunction "1_1") (pintype "passive"))
      (node (ref "R28") (pin "2") (pinfunction "2_2") (pintype "passive"))
      (node (ref "R32") (pin "2") (pinfunction "2_2") (pintype "passive"))
      (node (ref "U$3") (pin "5") (pinfunction "OUT_5") (pintype "bidirectional"))
    )
    (net (code "73") (name "unconnected-(IC3-A0-Pad1)") (class "Default")
      (node (ref "IC3") (pin "1") (pinfunction "A0_1") (pintype "passive"))
    )
    (net (code "74") (name "unconnected-(IC3-A1-Pad2)") (class "Default")
      (node (ref "IC3") (pin "2") (pinfunction "A1_2") (pintype "passive"))
    )
    (net (code "75") (name "unconnected-(IC3-A2-Pad3)") (class "Default")
      (node (ref "IC3") (pin "3") (pinfunction "A2_3") (pintype "passive"))
    )
    (net (code "76") (name "unconnected-(U$3-FB{slash}NC-Pad1)") (class "Default")
      (node (ref "U$3") (pin "1") (pinfunction "FB/NC_1") (pintype "bidirectional"))
    )
    (net (code "77") (name "unconnected-(U$3-NC-Pad3)") (class "Default")
      (node (ref "U$3") (pin "3") (pinfunction "NC_3") (pintype "bidirectional"))
    )
    (net (code "78") (name "unconnected-(U2-AIO0-Pad9)") (class "Default")
      (node (ref "U2") (pin "9") (pinfunction "AIO0_9") (pintype "bidirectional"))
    )
    (net (code "79") (name "unconnected-(U2-AIO1-Pad10)") (class "Default")
      (node (ref "U2") (pin "10") (pinfunction "AIO1_10") (pintype "bidirectional"))
    )
    (net (code "80") (name "unconnected-(U2-CLK-Pad19)") (class "Default")
      (node (ref "U2") (pin "19") (pinfunction "CLK_19") (pintype "bidirectional"))
    )
    (net (code "81") (name "unconnected-(U2-CSB-Pad16)") (class "Default")
      (node (ref "U2") (pin "16") (pinfunction "CSB_16") (pintype "bidirectional"))
    )
    (net (code "82") (name "unconnected-(U2-CTS-Pad3)") (class "Default")
      (node (ref "U2") (pin "3") (pinfunction "CTS_3") (pintype "bidirectional"))
    )
    (net (code "83") (name "unconnected-(U2-MISO-Pad18)") (class "Default")
      (node (ref "U2") (pin "18") (pinfunction "MISO_18") (pintype "bidirectional"))
    )
    (net (code "84") (name "unconnected-(U2-MOSI-Pad17)") (class "Default")
      (node (ref "U2") (pin "17") (pinfunction "MOSI_17") (pintype "bidirectional"))
    )
    (net (code "85") (name "unconnected-(U2-NC-Pad14)") (class "Default")
      (node (ref "U2") (pin "14") (pinfunction "NC_14") (pintype "bidirectional"))
    )
    (net (code "86") (name "unconnected-(U2-PCM_CLK-Pad5)") (class "Default")
      (node (ref "U2") (pin "5") (pinfunction "PCM_CLK_5") (pintype "bidirectional"))
    )
    (net (code "87") (name "unconnected-(U2-PCM_IN-Pad7)") (class "Default")
      (node (ref "U2") (pin "7") (pinfunction "PCM_IN_7") (pintype "bidirectional"))
    )
    (net (code "88") (name "unconnected-(U2-PCM_OUT-Pad6)") (class "Default")
      (node (ref "U2") (pin "6") (pinfunction "PCM_OUT_6") (pintype "bidirectional"))
    )
    (net (code "89") (name "unconnected-(U2-PCN_SYNC-Pad8)") (class "Default")
      (node (ref "U2") (pin "8") (pinfunction "PCN_SYNC_8") (pintype "bidirectional"))
    )
    (net (code "90") (name "unconnected-(U2-PIO0-Pad23)") (class "Default")
      (node (ref "U2") (pin "23") (pinfunction "PIO0_23") (pintype "bidirectional"))
    )
    (net (code "91") (name "unconnected-(U2-PIO1-Pad24)") (class "Default")
      (node (ref "U2") (pin "24") (pinfunction "PIO1_24") (pintype "bidirectional"))
    )
    (net (code "92") (name "unconnected-(U2-PIO2-Pad25)") (class "Default")
      (node (ref "U2") (pin "25") (pinfunction "PIO2_25") (pintype "bidirectional"))
    )
    (net (code "93") (name "unconnected-(U2-PIO3-Pad26)") (class "Default")
      (node (ref "U2") (pin "26") (pinfunction "PIO3_26") (pintype "bidirectional"))
    )
    (net (code "94") (name "unconnected-(U2-PIO4-Pad27)") (class "Default")
      (node (ref "U2") (pin "27") (pinfunction "PIO4_27") (pintype "bidirectional"))
    )
    (net (code "95") (name "unconnected-(U2-PIO5-Pad28)") (class "Default")
      (node (ref "U2") (pin "28") (pinfunction "PIO5_28") (pintype "bidirectional"))
    )
    (net (code "96") (name "unconnected-(U2-PIO6-Pad29)") (class "Default")
      (node (ref "U2") (pin "29") (pinfunction "PIO6_29") (pintype "bidirectional"))
    )
    (net (code "97") (name "unconnected-(U2-PIO7-Pad30)") (class "Default")
      (node (ref "U2") (pin "30") (pinfunction "PIO7_30") (pintype "bidirectional"))
    )
    (net (code "98") (name "unconnected-(U2-PIO8-Pad31)") (class "Default")
      (node (ref "U2") (pin "31") (pinfunction "PIO8_31") (pintype "bidirectional"))
    )
    (net (code "99") (name "unconnected-(U2-PIO9-Pad32)") (class "Default")
      (node (ref "U2") (pin "32") (pinfunction "PIO9_32") (pintype "bidirectional"))
    )
    (net (code "100") (name "unconnected-(U2-PIO10-Pad33)") (class "Default")
      (node (ref "U2") (pin "33") (pinfunction "PIO10_33") (pintype "bidirectional"))
    )
    (net (code "101") (name "unconnected-(U2-RTS-Pad4)") (class "Default")
      (node (ref "U2") (pin "4") (pinfunction "RTS_4") (pintype "bidirectional"))
    )
    (net (code "102") (name "unconnected-(U2-VBUSD+-Pad20)") (class "Default")
      (node (ref "U2") (pin "20") (pinfunction "VBUSD+_20") (pintype "bidirectional"))
    )
    (net (code "103") (name "unconnected-(U2-VBUSD--Pad15)") (class "Default")
      (node (ref "U2") (pin "15") (pinfunction "VBUSD-_15") (pintype "bidirectional"))
    )
  )
)
